# Analog_In_Filter.net
KiCad netlist of a schematic drawn in Altium Designer
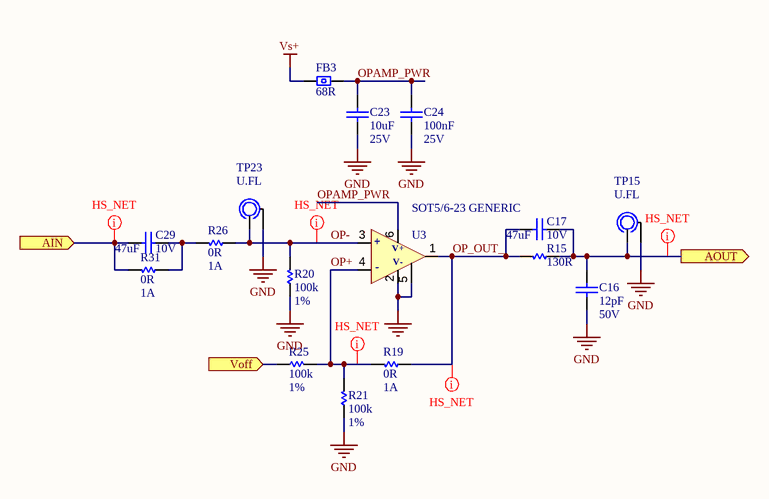
[diagram p0: Analog_In_Filter.SchDoc]

(export (version "E")
  (design (tool "Eeschema 10.0.6"))
  (components
    (comp (ref "C16")
      (value "12pF")
      (footprint "C0402")
      (description "Ceramic capacitor SMD-0402 12pF /50V C0G# J +-5%, Samsung, RoHS")
      (fields
        (field (name "MANUFACTURER") "Samsung")
        (field (name "MANUFACTURER PART NUMBER") "CL05C120JB5NNNC")
        (field (name "VOLTAGE") "50V")
      )
      (libsource (lib "LaserDiode_Analog") (part "CAP CER 12pF 50V C0G 0402"))
    )
    (comp (ref "C17")
      (value "47uF")
      (footprint "C1210")
      (description "CAP CER 47UF 10V 20% X7R 1210")
      (fields
        (field (name "MANUFACTURER") "Murata")
        (field (name "MANUFACTURER PART NUMBER") "GRM32ER71A476ME15L")
        (field (name "VOLTAGE RATING") "10V")
      )
      (libsource (lib "LaserDiode_Driver") (part "CAP CER 47uF 10V X7R 1210"))
    )
    (comp (ref "C23")
      (value "10uF")
      (footprint "c0805")
      (description "Cap Ceramic 10uF 25V X5R 10% SMD 0805 85°C Embossed T/R")
      (fields
        (field (name "MANUFACTURER") "Samsung")
        (field (name "MANUFACTURER PART NUMBER") "CL21A106KAYNNNE")
        (field (name "VOLTAGE RATING") "25V")
      )
      (libsource (lib "OPAMP_DEV_SOT5_6-23") (part "CAP CER 10uF 25V X5R 0805"))
    )
    (comp (ref "C24")
      (value "100nF")
      (footprint "C0402")
      (description "Cap Ceramic 0.1uF 25V X5R 10% Pad SMD 0402 85°C T/R / Multi Layer Ceramic Capacitor (MLCC)")
      (fields
        (field (name "MANUFACTURER") "Samsung")
        (field (name "MANUFACTURER PART NUMBER") "CL05A104KA5NNNC")
        (field (name "VOLTAGE RATING") "25V")
      )
      (libsource (lib "OPAMP_DEV_SOT5_6-23") (part "CAP CER 100nF 25V X5R 0402"))
    )
    (comp (ref "C29")
      (value "47uF")
      (footprint "C1210")
      (description "CAP CER 47UF 10V 20% X7R 1210")
      (fields
        (field (name "MANUFACTURER") "Murata")
        (field (name "MANUFACTURER PART NUMBER") "GRM32ER71A476ME15L")
        (field (name "VOLTAGE RATING") "10V")
      )
      (libsource (lib "LaserDiode_Driver") (part "CAP CER 47uF 10V X7R 1210"))
    )
    (comp (ref "FB3")
      (value "68R")
      (footprint "FB0402")
      (description "Ferrite Beads Multi-Layer 68Ohm 25% 100MHz 400mA 310mOhm DCR 0402 T/R")
      (fields
        (field (name "MANUFACTURER") "Taiyo Yuden")
        (field (name "MANUFACTURER PART NUMBER") "BK1005LL680-T")
      )
      (libsource (lib "MCU") (part "FB 68R 400mA 310mR 0402"))
    )
    (comp (ref "R15")
      (value "130R")
      (footprint "R0402")
      (description "Res General Purpose Thick Film 0402 130 Ohm 1% 1/16W ±100ppm/°C Molded SMD Paper T/R")
      (libsource (lib "LaserDiode_Analog") (part "RES 130R 1% 63mW 0402"))
    )
    (comp (ref "R19")
      (value "0R")
      (footprint "R0402")
      (description "GLOVE, POLYAMIDE, L/FREE, PU, SIZE 6 - More Details")
      (fields
        (field (name "MANUFACTURER") "Stackpole Electronics")
        (field (name "MANUFACTURER PART NUMBER") "RMCF0402ZT0R00")
        (field (name "CURRENT RATING") "1A")
      )
      (libsource (lib "LaserDiode_Analog") (part "RES 0R 63mW 0402"))
    )
    (comp (ref "R20")
      (value "100k")
      (footprint "r0402")
      (description "Res Thick Film 0402 100K Ohm 1% 0.063W ±100ppm/°C Molded SMD Paper T/R")
      (fields
        (field (name "MANUFACTURER") "Stackpole Electronics")
        (field (name "MANUFACTURER PART NUMBER") "RMCF0402FT100K")
        (field (name "TOLERANCE") "1%")
      )
      (libsource (lib "LaserDiode_Analog") (part "RES 100k 1% 63mW 0402"))
    )
    (comp (ref "R21")
      (value "100k")
      (footprint "r0402")
      (description "Res Thick Film 0402 100K Ohm 1% 0.063W ±100ppm/°C Molded SMD Paper T/R")
      (fields
        (field (name "MANUFACTURER") "Stackpole Electronics")
        (field (name "MANUFACTURER PART NUMBER") "RMCF0402FT100K")
        (field (name "TOLERANCE") "1%")
      )
      (libsource (lib "LaserDiode_Analog") (part "RES 100k 1% 63mW 0402"))
    )
    (comp (ref "R25")
      (value "100k")
      (footprint "r0402")
      (description "Res Thick Film 0402 100K Ohm 1% 0.063W ±100ppm/°C Molded SMD Paper T/R")
      (fields
        (field (name "MANUFACTURER") "Stackpole Electronics")
        (field (name "MANUFACTURER PART NUMBER") "RMCF0402FT100K")
        (field (name "TOLERANCE") "1%")
      )
      (libsource (lib "LaserDiode_Analog") (part "RES 100k 1% 63mW 0402"))
    )
    (comp (ref "R26")
      (value "0R")
      (footprint "R0402")
      (description "GLOVE, POLYAMIDE, L/FREE, PU, SIZE 6 - More Details")
      (fields
        (field (name "MANUFACTURER") "Stackpole Electronics")
        (field (name "MANUFACTURER PART NUMBER") "RMCF0402ZT0R00")
        (field (name "CURRENT RATING") "1A")
      )
      (libsource (lib "LaserDiode_Analog") (part "RES 0R 63mW 0402"))
    )
    (comp (ref "R31")
      (value "0R")
      (footprint "R0402")
      (description "GLOVE, POLYAMIDE, L/FREE, PU, SIZE 6 - More Details")
      (fields
        (field (name "MANUFACTURER") "Stackpole Electronics")
        (field (name "MANUFACTURER PART NUMBER") "RMCF0402ZT0R00")
        (field (name "CURRENT RATING") "1A")
      )
      (libsource (lib "LaserDiode_Analog") (part "RES 0R 63mW 0402"))
    )
    (comp (ref "TP15")
      (value "U.FL")
      (footprint "U.FL")
      (description "CONN U.FL RCPT STR 50 OHM SMD")
      (fields
        (field (name "MANUFACTURER") "Hirose")
        (field (name "MANUFACTURER PART NUMBER") "U.FL-R-SMT-1(80)")
      )
      (libsource (lib "OPAMP_DEV_SOT5_6-23") (part "TP U.FL"))
    )
    (comp (ref "TP23")
      (value "U.FL")
      (footprint "U.FL")
      (description "CONN U.FL RCPT STR 50 OHM SMD")
      (fields
        (field (name "MANUFACTURER") "Hirose")
        (field (name "MANUFACTURER PART NUMBER") "U.FL-R-SMT-1(80)")
      )
      (libsource (lib "OPAMP_DEV_SOT5_6-23") (part "TP U.FL"))
    )
    (comp (ref "U3")
      (value "SOT5/6-23 GENERIC")
      (footprint "SOT23-5/6_Modified")
      (libsource (lib "LaserDiode_Analog") (part "IC OPAMP SOT5/6-23 GENERIC"))
    )
  )
  (nets
    (net (code "1") (name "/AIN") (class "Default")
      (node (ref "C29") (pin "2") (pinfunction "2_2") (pintype "passive"))
      (node (ref "R31") (pin "2") (pinfunction "2_2") (pintype "passive"))
    )
    (net (code "2") (name "/AOUT") (class "Default")
      (node (ref "C16") (pin "2") (pinfunction "2_2") (pintype "passive"))
      (node (ref "C17") (pin "1") (pinfunction "1_1") (pintype "passive"))
      (node (ref "R15") (pin "1") (pinfunction "1_1") (pintype "passive"))
      (node (ref "TP15") (pin "1") (pinfunction "1_1") (pintype "passive"))
    )
    (net (code "3") (name "/OP+") (class "Default")
      (node (ref "R19") (pin "2") (pinfunction "2_2") (pintype "passive"))
      (node (ref "R21") (pin "2") (pinfunction "2_2") (pintype "passive"))
      (node (ref "R25") (pin "2") (pinfunction "2_2") (pintype "passive"))
      (node (ref "U3") (pin "4") (pinfunction "-_4") (pintype "passive"))
    )
    (net (code "4") (name "/OP-") (class "Default")
      (node (ref "R20") (pin "2") (pinfunction "2_2") (pintype "passive"))
      (node (ref "R26") (pin "1") (pinfunction "1_1") (pintype "passive"))
      (node (ref "TP23") (pin "1") (pinfunction "1_1") (pintype "passive"))
      (node (ref "U3") (pin "3") (pinfunction "+_3") (pintype "passive"))
    )
    (net (code "5") (name "/OPAMP_PWR") (class "Default")
      (node (ref "C23") (pin "2") (pinfunction "2_2") (pintype "passive"))
      (node (ref "C24") (pin "1") (pinfunction "1_1") (pintype "passive"))
      (node (ref "FB3") (pin "1") (pintype "passive"))
      (node (ref "U3") (pin "6") (pinfunction "V+_6") (pintype "passive"))
    )
    (net (code "6") (name "/OP_OUT_") (class "Default")
      (node (ref "C17") (pin "2") (pinfunction "2_2") (pintype "passive"))
      (node (ref "R15") (pin "2") (pinfunction "2_2") (pintype "passive"))
      (node (ref "R19") (pin "1") (pinfunction "1_1") (pintype "passive"))
      (node (ref "U3") (pin "1") (pinfunction "1_1") (pintype "passive"))
    )
    (net (code "7") (name "/Voff") (class "Default")
      (node (ref "R25") (pin "1") (pinfunction "1_1") (pintype "passive"))
    )
    (net (code "8") (name "GND") (class "Default")
      (node (ref "C16") (pin "1") (pinfunction "1_1") (pintype "passive"))
      (node (ref "C23") (pin "1") (pinfunction "1_1") (pintype "passive"))
      (node (ref "C24") (pin "2") (pinfunction "2_2") (pintype "passive"))
      (node (ref "R20") (pin "1") (pinfunction "1_1") (pintype "passive"))
      (node (ref "R21") (pin "1") (pinfunction "1_1") (pintype "passive"))
      (node (ref "TP15") (pin "0") (pinfunction "0_0") (pintype "passive"))
      (node (ref "TP23") (pin "0") (pinfunction "0_0") (pintype "passive"))
      (node (ref "U3") (pin "2") (pinfunction "V-_2") (pintype "passive"))
      (node (ref "U3") (pin "5") (pinfunction "1_5") (pintype "passive"))
    )
    (net (code "9") (name "Net-(C29-Pad1)") (class "Default")
      (node (ref "C29") (pin "1") (pinfunction "1_1") (pintype "passive"))
      (node (ref "R26") (pin "2") (pinfunction "2_2") (pintype "passive"))
      (node (ref "R31") (pin "1") (pinfunction "1_1") (pintype "passive"))
    )
    (net (code "10") (name "Vs+") (class "Default") (node (ref "FB3") (pin "2") (pintype "passive")))
  )
)
